# remote_control.net
KiCad netlist of a schematic drawn in Altium Designer
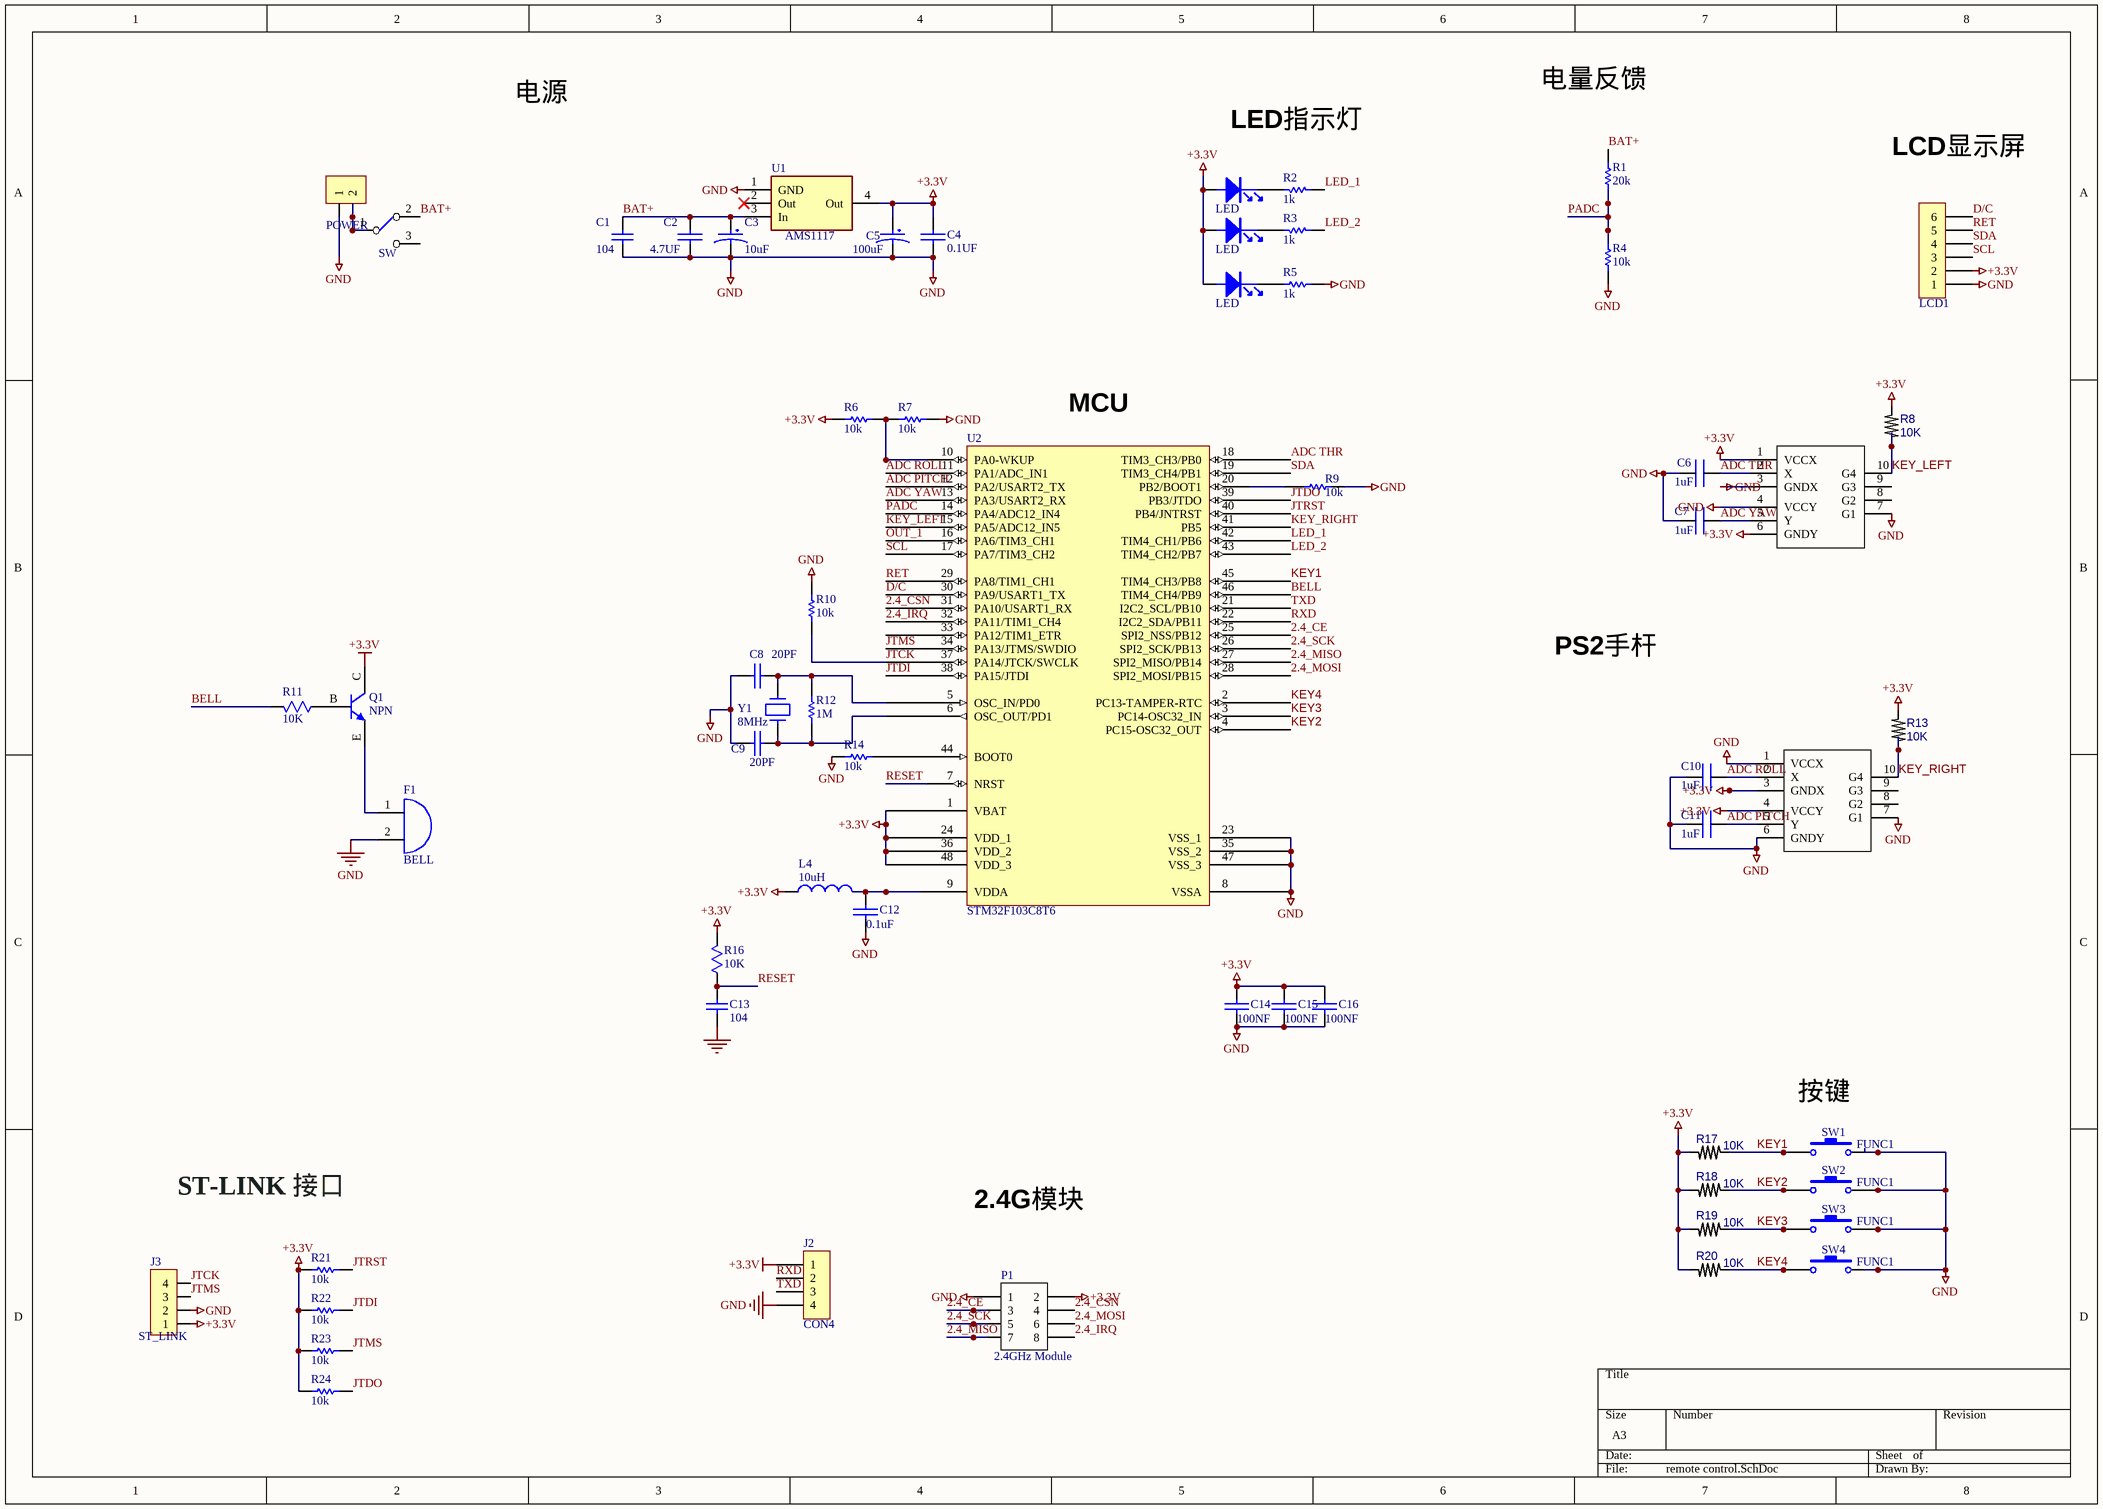
[diagram p0: remote control.SchDoc]

(export (version "E")
  (design (tool "Eeschema 10.0.6"))
  (components
    (comp (ref "C1")
      (value "104")
      (footprint "0805C")
      (description "Capacitor")
      (fields (field (name "PUBLISHER") "Altium Limited"))
      (libsource (lib "*") (part "Cap"))
    )
    (comp (ref "C2")
      (value "4.7UF")
      (footprint "1206C")
      (description "Capacitor/小容量电容")
      (libsource (lib "狗尾巴草设计室") (part "CAP"))
    )
    (comp (ref "C3")
      (value "CAPE")
      (footprint "C_EC")
      (fields (field (name "VAL") "10uF"))
      (libsource (lib "CommonSCH") (part "CAPE"))
    )
    (comp (ref "C4")
      (value "0.1UF")
      (footprint "0805C")
      (description "Capacitor/小容量电容")
      (libsource (lib "狗尾巴草设计室") (part "CAP"))
    )
    (comp (ref "C5")
      (value "CAPE")
      (footprint "C_ED8")
      (fields (field (name "VAL") "100uF"))
      (libsource (lib "CommonSCH") (part "CAPE"))
    )
    (comp (ref "C6") (value "1uF") (footprint "0805C") (libsource (lib "分立元件") (part "CAP")))
    (comp (ref "C7") (value "1uF") (footprint "0805") (libsource (lib "分立元件") (part "CAP")))
    (comp (ref "C8")
      (value "20PF")
      (footprint "0805C")
      (description "Capacitor/小容量电容")
      (libsource (lib "狗尾巴草设计室") (part "CAP"))
    )
    (comp (ref "C9")
      (value "20PF")
      (footprint "0805C")
      (description "Capacitor/小容量电容")
      (libsource (lib "狗尾巴草设计室") (part "CAP"))
    )
    (comp (ref "C10") (value "1uF") (footprint "0805") (libsource (lib "分立元件") (part "CAP")))
    (comp (ref "C11") (value "1uF") (footprint "0805") (libsource (lib "分立元件") (part "CAP")))
    (comp (ref "C12")
      (value "0.1uF")
      (footprint "0805C")
      (description "Capacitor/小容量电容")
      (libsource (lib "狗尾巴草设计室") (part "CAP"))
    )
    (comp (ref "C13")
      (value "104")
      (footprint "0805C")
      (description "GRM39 X7R102K50PT")
      (fields (field (name "PUBLISHER") "Altium Limited"))
      (libsource (lib "Miscellaneous Devices") (part "CAP"))
    )
    (comp (ref "C14")
      (value "100NF")
      (footprint "0805C")
      (description "Capacitor/小容量电容")
      (libsource (lib "狗尾巴草设计室") (part "CAP"))
    )
    (comp (ref "C15")
      (value "100NF")
      (footprint "0805C")
      (description "Capacitor/小容量电容")
      (libsource (lib "狗尾巴草设计室") (part "CAP"))
    )
    (comp (ref "C16")
      (value "100NF")
      (footprint "0805C")
      (description "Capacitor/小容量电容")
      (libsource (lib "狗尾巴草设计室") (part "CAP"))
    )
    (comp (ref "control_L1")
      (value "Joy Stick")
      (footprint "PS2")
      (description "Header, 10-Pin, Dual row")
      (fields (field (name "PUBLISHER") "Altium Limited"))
      (libsource (lib "1RMB") (part "Joy Stick"))
    )
    (comp (ref "control_R1")
      (value "Joy Stick")
      (footprint "PS2")
      (description "Header, 10-Pin, Dual row")
      (fields (field (name "PUBLISHER") "Altium Limited"))
      (libsource (lib "1RMB") (part "Joy Stick"))
    )
    (comp (ref "F1") (value "BELL") (footprint "BELL") (libsource (lib "狗尾巴草设计室") (part "BELL")))
    (comp (ref "J1") (value "POWER") (footprint "SIP2") (libsource (lib "狗尾巴草设计室") (part "SIP2")))
    (comp (ref "J2") (value "CON4") (footprint "SIP4") (libsource (lib "常用元件库") (part "CON4")))
    (comp (ref "J3") (value "ST_LINK") (footprint "P4_2.54-1") (libsource (lib "狗尾巴草设计室") (part "SIP4")))
    (comp (ref "L1") (value "LED") (footprint "0805D") (libsource (lib "ZF_library") (part "LED")))
    (comp (ref "L2") (value "LED") (footprint "0805D") (libsource (lib "ZF_library") (part "LED")))
    (comp (ref "L3") (value "LED") (footprint "0805D") (libsource (lib "ZF_library") (part "LED")))
    (comp (ref "L4")
      (value "INDUCTOR")
      (footprint "0805")
      (fields (field (name "VAL") "10uH"))
      (libsource (lib "SCH") (part "INDUCTOR"))
    )
    (comp (ref "LCD1") (value "CON6") (footprint "SIP6") (libsource (lib "常用元件库") (part "CON6")))
    (comp (ref "P1")
      (value "2.4GHz Module")
      (footprint "2.4Gmedal")
      (description "Header, 10-Pin, Dual row")
      (fields (field (name "PUBLISHER") "Altium Limited"))
      (libsource (lib "*") (part "Header 4X2"))
    )
    (comp (ref "Q1") (value "NPN") (footprint "SOT-23(BEC-123)") (libsource (lib "狗尾巴草设计室") (part "NPN")))
    (comp (ref "R1")
      (value "RES")
      (footprint "0805")
      (description "Semiconductor Resistor")
      (fields (field (name "VAL") "20k") (field (name "PUBLISHER") "*"))
      (libsource (lib "SCH") (part "RES"))
    )
    (comp (ref "R2")
      (value "1k")
      (footprint "0805R")
      (description "Resistor")
      (fields (field (name "Comment") "Res1") (field (name "PUBLISHER") "Altium Limited"))
      (libsource (lib "ZF_library") (part "Res1"))
    )
    (comp (ref "R3")
      (value "1k")
      (footprint "0805R")
      (description "Resistor")
      (fields (field (name "Comment") "Res1") (field (name "PUBLISHER") "Altium Limited"))
      (libsource (lib "ZF_library") (part "Res1"))
    )
    (comp (ref "R4")
      (value "RES")
      (footprint "0805")
      (description "Semiconductor Resistor")
      (fields (field (name "VAL") "10k") (field (name "PUBLISHER") "*"))
      (libsource (lib "SCH") (part "RES"))
    )
    (comp (ref "R5")
      (value "1k")
      (footprint "0805R")
      (description "Resistor")
      (fields (field (name "Comment") "Res1") (field (name "PUBLISHER") "Altium Limited"))
      (libsource (lib "SCHLIB1") (part "Res1"))
    )
    (comp (ref "R6")
      (value "RES")
      (footprint "0805")
      (description "Semiconductor Resistor")
      (fields (field (name "VAL") "10k") (field (name "PUBLISHER") "*"))
      (libsource (lib "SCH") (part "RES"))
    )
    (comp (ref "R7")
      (value "RES")
      (footprint "0805R")
      (description "Semiconductor Resistor")
      (fields (field (name "VAL") "10k") (field (name "PUBLISHER") "*"))
      (libsource (lib "SCH") (part "RES"))
    )
    (comp (ref "R8") (value "10K") (footprint "0805R") (libsource (lib "*") (part "RES")))
    (comp (ref "R9")
      (value "RES")
      (footprint "0805R")
      (description "Semiconductor Resistor")
      (fields (field (name "VAL") "10k") (field (name "PUBLISHER") "*"))
      (libsource (lib "SCH") (part "RES"))
    )
    (comp (ref "R10")
      (value "RES")
      (footprint "0805R")
      (description "Semiconductor Resistor")
      (fields (field (name "VAL") "10k") (field (name "PUBLISHER") "*"))
      (libsource (lib "SCH") (part "RES"))
    )
    (comp (ref "R11") (value "10K") (footprint "0805R") (libsource (lib "YT1_SCH_99SE") (part "RES")))
    (comp (ref "R12")
      (value "RES")
      (footprint "0805R")
      (description "Semiconductor Resistor")
      (fields (field (name "VAL") "1M") (field (name "PUBLISHER") "*"))
      (libsource (lib "SCH") (part "RES"))
    )
    (comp (ref "R13") (value "10K") (footprint "0805R") (libsource (lib "*") (part "RES")))
    (comp (ref "R14")
      (value "RES")
      (footprint "0805R")
      (description "Semiconductor Resistor")
      (fields (field (name "VAL") "10k") (field (name "PUBLISHER") "*"))
      (libsource (lib "SCH") (part "RES"))
    )
    (comp (ref "R16") (value "10K") (footprint "0805R") (libsource (lib "YT1_SCH_99SE") (part "RES")))
    (comp (ref "R17") (value "10K") (footprint "0805C") (libsource (lib "*") (part "RES")))
    (comp (ref "R18") (value "10K") (footprint "0805C") (libsource (lib "*") (part "RES")))
    (comp (ref "R19") (value "10K") (footprint "0805C") (libsource (lib "*") (part "RES")))
    (comp (ref "R20") (value "10K") (footprint "0805C") (libsource (lib "*") (part "RES")))
    (comp (ref "R21")
      (value "RES")
      (footprint "0805R")
      (description "Semiconductor Resistor")
      (fields (field (name "VAL") "10k") (field (name "PUBLISHER") "*"))
      (libsource (lib "SCH") (part "RES"))
    )
    (comp (ref "R22")
      (value "RES")
      (footprint "0805R")
      (description "Semiconductor Resistor")
      (fields (field (name "VAL") "10k") (field (name "PUBLISHER") "*"))
      (libsource (lib "SCH") (part "RES"))
    )
    (comp (ref "R23")
      (value "RES")
      (footprint "0805R")
      (description "Semiconductor Resistor")
      (fields (field (name "VAL") "10k") (field (name "PUBLISHER") "*"))
      (libsource (lib "SCH") (part "RES"))
    )
    (comp (ref "R24")
      (value "RES")
      (footprint "0805R")
      (description "Semiconductor Resistor")
      (fields (field (name "VAL") "10k") (field (name "PUBLISHER") "*"))
      (libsource (lib "SCH") (part "RES"))
    )
    (comp (ref "S1")
      (value "SW")
      (footprint "KEY_DIP_12D07-4")
      (libsource (lib "AD_Lib_temp") (part "SW_拨动_小型"))
    )
    (comp (ref "SW1")
      (value "FUNC1")
      (footprint "KEY_SIM_6X6")
      (description "Switch")
      (fields (field (name "PUBLISHER") "Altium Limited"))
      (libsource (lib "Miscellaneous Devices") (part "SW-PB"))
    )
    (comp (ref "SW2")
      (value "FUNC1")
      (footprint "KEY_SIM_6X6")
      (description "Switch")
      (fields (field (name "PUBLISHER") "Altium Limited"))
      (libsource (lib "Miscellaneous Devices") (part "SW-PB"))
    )
    (comp (ref "SW3")
      (value "FUNC1")
      (footprint "KEY_SIM_6X6")
      (description "Switch")
      (fields (field (name "PUBLISHER") "Altium Limited"))
      (libsource (lib "Miscellaneous Devices") (part "SW-PB"))
    )
    (comp (ref "SW4")
      (value "FUNC1")
      (footprint "KEY_SIM_6X6")
      (description "Switch")
      (fields (field (name "PUBLISHER") "Altium Limited"))
      (libsource (lib "Miscellaneous Devices") (part "SW-PB"))
    )
    (comp (ref "U1")
      (value "AMS1117")
      (footprint "SOT223")
      (description "Header, 2-Pin")
      (fields (field (name "PUBLISHER") "*"))
      (libsource (lib "CommonSCH") (part "AMS1117"))
    )
    (comp (ref "U2")
      (value "STM32F103C8T6")
      (footprint "LQFP48")
      (description "STM32 ARM-based 32-bit MCU with 64 Kbytes Flash, 48-pin LQFP, Industrial Temperature")
      (fields (field (name "PUBLISHER") "*"))
      (libsource (lib "ZF_library") (part "STM32F103C8T6"))
    )
    (comp (ref "Y1")
      (value "CRYSTAL1")
      (footprint "HC-49T")
      (fields (field (name "VAL") "8MHz"))
      (libsource (lib "SCH") (part "CRYSTAL1"))
    )
  )
  (nets
    (net (code "1") (name "+3.3V") (class "Default")
      (node (ref "C14") (pin "1") (pinfunction "1_1") (pintype "passive"))
      (node (ref "C15") (pin "1") (pinfunction "1_1") (pintype "passive"))
      (node (ref "C16") (pin "1") (pinfunction "1_1") (pintype "passive"))
      (node (ref "C4") (pin "1") (pinfunction "1_1") (pintype "passive"))
      (node (ref "C5") (pin "1") (pinfunction "1_1") (pintype "passive"))
      (node (ref "J2") (pin "1") (pinfunction "1_1") (pintype "passive"))
      (node (ref "J3") (pin "1") (pinfunction "1_1") (pintype "passive"))
      (node (ref "L1") (pin "1") (pintype "passive"))
      (node (ref "L2") (pin "1") (pintype "passive"))
      (node (ref "L3") (pin "1") (pintype "passive"))
      (node (ref "L4") (pin "1") (pinfunction "1_1") (pintype "passive"))
      (node (ref "LCD1") (pin "2") (pinfunction "2_2") (pintype "passive"))
      (node (ref "P1") (pin "2") (pinfunction "2_2") (pintype "passive"))
      (node (ref "Q1") (pin "C") (pinfunction "C_C") (pintype "passive"))
      (node (ref "R13") (pin "2") (pinfunction "2_2") (pintype "passive"))
      (node (ref "R16") (pin "2") (pinfunction "2_2") (pintype "passive"))
      (node (ref "R17") (pin "1") (pinfunction "1_1") (pintype "passive"))
      (node (ref "R18") (pin "1") (pinfunction "1_1") (pintype "passive"))
      (node (ref "R19") (pin "1") (pinfunction "1_1") (pintype "passive"))
      (node (ref "R20") (pin "1") (pinfunction "1_1") (pintype "passive"))
      (node (ref "R21") (pin "2") (pinfunction "2_2") (pintype "passive"))
      (node (ref "R22") (pin "2") (pinfunction "2_2") (pintype "passive"))
      (node (ref "R23") (pin "2") (pinfunction "2_2") (pintype "passive"))
      (node (ref "R24") (pin "2") (pinfunction "2_2") (pintype "passive"))
      (node (ref "R6") (pin "2") (pinfunction "2_2") (pintype "passive"))
      (node (ref "R8") (pin "2") (pinfunction "2_2") (pintype "passive"))
      (node (ref "U1") (pin "4") (pinfunction "Out_4") (pintype "passive"))
      (node (ref "U2") (pin "1") (pinfunction "VBAT_1") (pintype "power_in"))
      (node (ref "U2") (pin "24") (pinfunction "VDD_1_24") (pintype "power_in"))
      (node (ref "U2") (pin "36") (pinfunction "VDD_2_36") (pintype "power_in"))
      (node (ref "U2") (pin "48") (pinfunction "VDD_3_48") (pintype "power_in"))
      (node (ref "control_L1") (pin "1") (pinfunction "VCCX_1") (pintype "passive"))
      (node (ref "control_L1") (pin "6") (pinfunction "GNDY_6") (pintype "passive"))
      (node (ref "control_R1") (pin "3") (pinfunction "GNDX_3") (pintype "passive"))
      (node (ref "control_R1") (pin "4") (pinfunction "VCCY_4") (pintype "passive"))
    )
    (net (code "2") (name "/2.4_CE") (class "Default")
      (node (ref "P1") (pin "3") (pinfunction "3_3") (pintype "passive"))
      (node (ref "U2") (pin "25") (pinfunction "SPI2_NSS/PB12_25") (pintype "bidirectional"))
    )
    (net (code "3") (name "/2.4_CSN") (class "Default")
      (node (ref "P1") (pin "4") (pinfunction "4_4") (pintype "passive"))
      (node (ref "U2") (pin "31") (pinfunction "PA10/USART1_RX_31") (pintype "bidirectional"))
    )
    (net (code "4") (name "/2.4_IRQ") (class "Default")
      (node (ref "P1") (pin "8") (pinfunction "8_8") (pintype "passive"))
      (node (ref "U2") (pin "32") (pinfunction "PA11/TIM1_CH4_32") (pintype "bidirectional"))
    )
    (net (code "5") (name "/2.4_MISO") (class "Default")
      (node (ref "P1") (pin "7") (pinfunction "7_7") (pintype "passive"))
      (node (ref "U2") (pin "27") (pinfunction "SPI2_MISO/PB14_27") (pintype "bidirectional"))
    )
    (net (code "6") (name "/2.4_MOSI") (class "Default")
      (node (ref "P1") (pin "6") (pinfunction "6_6") (pintype "passive"))
      (node (ref "U2") (pin "28") (pinfunction "SPI2_MOSI/PB15_28") (pintype "bidirectional"))
    )
    (net (code "7") (name "/2.4_SCK") (class "Default")
      (node (ref "P1") (pin "5") (pinfunction "5_5") (pintype "passive"))
      (node (ref "U2") (pin "26") (pinfunction "SPI2_SCK/PB13_26") (pintype "bidirectional"))
    )
    (net (code "8") (name "/ADC PITCH") (class "Default")
      (node (ref "C11") (pin "2") (pinfunction "2_2") (pintype "passive"))
      (node (ref "U2") (pin "12") (pinfunction "PA2/USART2_TX_12") (pintype "bidirectional"))
      (node (ref "control_R1") (pin "5") (pinfunction "Y_5") (pintype "passive"))
    )
    (net (code "9") (name "/ADC ROLL") (class "Default")
      (node (ref "C10") (pin "2") (pinfunction "2_2") (pintype "passive"))
      (node (ref "U2") (pin "11") (pinfunction "PA1/ADC_IN1_11") (pintype "bidirectional"))
      (node (ref "control_R1") (pin "2") (pinfunction "X_2") (pintype "passive"))
    )
    (net (code "10") (name "/ADC THR") (class "Default")
      (node (ref "C6") (pin "2") (pinfunction "2_2") (pintype "passive"))
      (node (ref "U2") (pin "18") (pinfunction "TIM3_CH3/PB0_18") (pintype "bidirectional"))
      (node (ref "control_L1") (pin "2") (pinfunction "X_2") (pintype "passive"))
    )
    (net (code "11") (name "/ADC YAW") (class "Default")
      (node (ref "C7") (pin "2") (pinfunction "2_2") (pintype "passive"))
      (node (ref "U2") (pin "13") (pinfunction "PA3/USART2_RX_13") (pintype "bidirectional"))
      (node (ref "control_L1") (pin "5") (pinfunction "Y_5") (pintype "passive"))
    )
    (net (code "12") (name "/BAT+") (class "Default")
      (node (ref "C1") (pin "1") (pinfunction "1_1") (pintype "passive"))
      (node (ref "C2") (pin "1") (pinfunction "1_1") (pintype "passive"))
      (node (ref "C3") (pin "1") (pinfunction "1_1") (pintype "passive"))
      (node (ref "R1") (pin "2") (pinfunction "2_2") (pintype "passive"))
      (node (ref "S1") (pin "2") (pinfunction "1_2") (pintype "passive"))
      (node (ref "U1") (pin "3") (pinfunction "In_3") (pintype "passive"))
    )
    (net (code "13") (name "/BELL") (class "Default")
      (node (ref "R11") (pin "2") (pinfunction "2_2") (pintype "passive"))
      (node (ref "U2") (pin "46") (pinfunction "TIM4_CH4/PB9_46") (pintype "bidirectional"))
    )
    (net (code "14") (name "/D{slash}C") (class "Default")
      (node (ref "LCD1") (pin "6") (pinfunction "6_6") (pintype "passive"))
      (node (ref "U2") (pin "30") (pinfunction "PA9/USART1_TX_30") (pintype "bidirectional"))
    )
    (net (code "15") (name "/JTCK") (class "Default")
      (node (ref "J3") (pin "4") (pinfunction "4_4") (pintype "passive"))
      (node (ref "R10") (pin "1") (pinfunction "1_1") (pintype "passive"))
      (node (ref "U2") (pin "37") (pinfunction "PA14/JTCK/SWCLK_37") (pintype "bidirectional"))
    )
    (net (code "16") (name "/JTDI") (class "Default")
      (node (ref "R22") (pin "1") (pinfunction "1_1") (pintype "passive"))
      (node (ref "U2") (pin "38") (pinfunction "PA15/JTDI_38") (pintype "bidirectional"))
    )
    (net (code "17") (name "/JTDO") (class "Default")
      (node (ref "R24") (pin "1") (pinfunction "1_1") (pintype "passive"))
      (node (ref "U2") (pin "39") (pinfunction "PB3/JTDO_39") (pintype "bidirectional"))
    )
    (net (code "18") (name "/JTMS") (class "Default")
      (node (ref "J3") (pin "3") (pinfunction "3_3") (pintype "passive"))
      (node (ref "R23") (pin "1") (pinfunction "1_1") (pintype "passive"))
      (node (ref "U2") (pin "34") (pinfunction "PA13/JTMS/SWDIO_34") (pintype "bidirectional"))
    )
    (net (code "19") (name "/JTRST") (class "Default")
      (node (ref "R21") (pin "1") (pinfunction "1_1") (pintype "passive"))
      (node (ref "U2") (pin "40") (pinfunction "PB4/JNTRST_40") (pintype "bidirectional"))
    )
    (net (code "20") (name "/KEY1") (class "Default")
      (node (ref "R17") (pin "2") (pinfunction "2_2") (pintype "passive"))
      (node (ref "SW1") (pin "2") (pinfunction "2_2") (pintype "passive"))
      (node (ref "U2") (pin "45") (pinfunction "TIM4_CH3/PB8_45") (pintype "bidirectional"))
    )
    (net (code "21") (name "/KEY2") (class "Default")
      (node (ref "R18") (pin "2") (pinfunction "2_2") (pintype "passive"))
      (node (ref "SW2") (pin "2") (pinfunction "2_2") (pintype "passive"))
      (node (ref "U2") (pin "4") (pinfunction "PC15-OSC32_OUT_4") (pintype "bidirectional"))
    )
    (net (code "22") (name "/KEY3") (class "Default")
      (node (ref "R19") (pin "2") (pinfunction "2_2") (pintype "passive"))
      (node (ref "SW3") (pin "2") (pinfunction "2_2") (pintype "passive"))
      (node (ref "U2") (pin "3") (pinfunction "PC14-OSC32_IN_3") (pintype "bidirectional"))
    )
    (net (code "23") (name "/KEY4") (class "Default")
      (node (ref "R20") (pin "2") (pinfunction "2_2") (pintype "passive"))
      (node (ref "SW4") (pin "2") (pinfunction "2_2") (pintype "passive"))
      (node (ref "U2") (pin "2") (pinfunction "PC13-TAMPER-RTC_2") (pintype "bidirectional"))
    )
    (net (code "24") (name "/KEY_LEFT") (class "Default")
      (node (ref "R8") (pin "1") (pinfunction "1_1") (pintype "passive"))
      (node (ref "U2") (pin "15") (pinfunction "PA5/ADC12_IN5_15") (pintype "bidirectional"))
      (node (ref "control_L1") (pin "10") (pinfunction "G4_10") (pintype "passive"))
    )
    (net (code "25") (name "/KEY_RIGHT") (class "Default")
      (node (ref "R13") (pin "1") (pinfunction "1_1") (pintype "passive"))
      (node (ref "U2") (pin "41") (pinfunction "PB5_41") (pintype "bidirectional"))
      (node (ref "control_R1") (pin "10") (pinfunction "G4_10") (pintype "passive"))
    )
    (net (code "26") (name "/LED_1") (class "Default")
      (node (ref "R2") (pin "1") (pinfunction "1_1") (pintype "passive"))
      (node (ref "U2") (pin "42") (pinfunction "TIM4_CH1/PB6_42") (pintype "bidirectional"))
    )
    (net (code "27") (name "/LED_2") (class "Default")
      (node (ref "R3") (pin "1") (pinfunction "1_1") (pintype "passive"))
      (node (ref "U2") (pin "43") (pinfunction "TIM4_CH2/PB7_43") (pintype "bidirectional"))
    )
    (net (code "28") (name "/OUT_1") (class "Default")
      (node (ref "U2") (pin "16") (pinfunction "PA6/TIM3_CH1_16") (pintype "bidirectional"))
    )
    (net (code "29") (name "/PADC") (class "Default")
      (node (ref "R1") (pin "1") (pinfunction "1_1") (pintype "passive"))
      (node (ref "R4") (pin "2") (pinfunction "2_2") (pintype "passive"))
      (node (ref "U2") (pin "14") (pinfunction "PA4/ADC12_IN4_14") (pintype "bidirectional"))
    )
    (net (code "30") (name "/RESET") (class "Default")
      (node (ref "C13") (pin "2") (pinfunction "2_2") (pintype "passive"))
      (node (ref "R16") (pin "1") (pinfunction "1_1") (pintype "passive"))
      (node (ref "U2") (pin "7") (pinfunction "NRST_7") (pintype "bidirectional"))
    )
    (net (code "31") (name "/RET") (class "Default")
      (node (ref "LCD1") (pin "5") (pinfunction "5_5") (pintype "passive"))
      (node (ref "U2") (pin "29") (pinfunction "PA8/TIM1_CH1_29") (pintype "bidirectional"))
    )
    (net (code "32") (name "/RXD") (class "Default")
      (node (ref "J2") (pin "2") (pinfunction "2_2") (pintype "passive"))
      (node (ref "U2") (pin "22") (pinfunction "I2C2_SDA/PB11_22") (pintype "bidirectional"))
    )
    (net (code "33") (name "/SCL") (class "Default")
      (node (ref "LCD1") (pin "3") (pinfunction "3_3") (pintype "passive"))
      (node (ref "U2") (pin "17") (pinfunction "PA7/TIM3_CH2_17") (pintype "bidirectional"))
    )
    (net (code "34") (name "/SDA") (class "Default")
      (node (ref "LCD1") (pin "4") (pinfunction "4_4") (pintype "passive"))
      (node (ref "U2") (pin "19") (pinfunction "TIM3_CH4/PB1_19") (pintype "bidirectional"))
    )
    (net (code "35") (name "/TXD") (class "Default")
      (node (ref "J2") (pin "3") (pinfunction "3_3") (pintype "passive"))
      (node (ref "U2") (pin "21") (pinfunction "I2C2_SCL/PB10_21") (pintype "bidirectional"))
    )
    (net (code "36") (name "GND") (class "Default")
      (node (ref "C1") (pin "2") (pinfunction "2_2") (pintype "passive"))
      (node (ref "C10") (pin "1") (pinfunction "1_1") (pintype "passive"))
      (node (ref "C11") (pin "1") (pinfunction "1_1") (pintype "passive"))
      (node (ref "C12") (pin "2") (pinfunction "2_2") (pintype "passive"))
      (node (ref "C13") (pin "1") (pinfunction "1_1") (pintype "passive"))
      (node (ref "C14") (pin "2") (pinfunction "2_2") (pintype "passive"))
      (node (ref "C15") (pin "2") (pinfunction "2_2") (pintype "passive"))
      (node (ref "C16") (pin "2") (pinfunction "2_2") (pintype "passive"))
      (node (ref "C2") (pin "2") (pinfunction "2_2") (pintype "passive"))
      (node (ref "C3") (pin "2") (pinfunction "2_2") (pintype "passive"))
      (node (ref "C4") (pin "2") (pinfunction "2_2") (pintype "passive"))
      (node (ref "C5") (pin "2") (pinfunction "2_2") (pintype "passive"))
      (node (ref "C6") (pin "1") (pinfunction "1_1") (pintype "passive"))
      (node (ref "C7") (pin "1") (pinfunction "1_1") (pintype "passive"))
      (node (ref "C8") (pin "1") (pinfunction "1_1") (pintype "passive"))
      (node (ref "C9") (pin "1") (pinfunction "1_1") (pintype "passive"))
      (node (ref "F1") (pin "2") (pinfunction "B_2") (pintype "passive"))
      (node (ref "J1") (pin "1") (pinfunction "1_1") (pintype "passive"))
      (node (ref "J2") (pin "4") (pinfunction "4_4") (pintype "passive"))
      (node (ref "J3") (pin "2") (pinfunction "2_2") (pintype "passive"))
      (node (ref "LCD1") (pin "1") (pinfunction "1_1") (pintype "passive"))
      (node (ref "P1") (pin "1") (pinfunction "1_1") (pintype "passive"))
      (node (ref "R10") (pin "2") (pinfunction "2_2") (pintype "passive"))
      (node (ref "R14") (pin "2") (pinfunction "2_2") (pintype "passive"))
      (node (ref "R4") (pin "1") (pinfunction "1_1") (pintype "passive"))
      (node (ref "R5") (pin "1") (pinfunction "1_1") (pintype "passive"))
      (node (ref "R7") (pin "1") (pinfunction "1_1") (pintype "passive"))
      (node (ref "R9") (pin "2") (pinfunction "2_2") (pintype "passive"))
      (node (ref "SW1") (pin "1") (pinfunction "1_1") (pintype "passive"))
      (node (ref "SW2") (pin "1") (pinfunction "1_1") (pintype "passive"))
      (node (ref "SW3") (pin "1") (pinfunction "1_1") (pintype "passive"))
      (node (ref "SW4") (pin "1") (pinfunction "1_1") (pintype "passive"))
      (node (ref "U1") (pin "1") (pinfunction "GND_1") (pintype "passive"))
      (node (ref "U2") (pin "23") (pinfunction "VSS_1_23") (pintype "power_in"))
      (node (ref "U2") (pin "35") (pinfunction "VSS_2_35") (pintype "power_in"))
      (node (ref "U2") (pin "47") (pinfunction "VSS_3_47") (pintype "power_in"))
      (node (ref "U2") (pin "8") (pinfunction "VSSA_8") (pintype "power_in"))
      (node (ref "control_L1") (pin "3") (pinfunction "GNDX_3") (pintype "passive"))
      (node (ref "control_L1") (pin "4") (pinfunction "VCCY_4") (pintype "passive"))
      (node (ref "control_L1") (pin "7") (pinfunction "G1_7") (pintype "passive"))
      (node (ref "control_R1") (pin "1") (pinfunction "VCCX_1") (pintype "passive"))
      (node (ref "control_R1") (pin "6") (pinfunction "GNDY_6") (pintype "passive"))
      (node (ref "control_R1") (pin "7") (pinfunction "G1_7") (pintype "passive"))
    )
    (net (code "37") (name "Net-(F1-A)") (class "Default")
      (node (ref "F1") (pin "1") (pinfunction "A_1") (pintype "passive"))
      (node (ref "Q1") (pin "E") (pinfunction "E_E") (pintype "passive"))
    )
    (net (code "38") (name "Net-(L1-Pad2)") (class "Default")
      (node (ref "L1") (pin "2") (pintype "passive"))
      (node (ref "R2") (pin "2") (pinfunction "2_2") (pintype "passive"))
    )
    (net (code "39") (name "Net-(L2-Pad2)") (class "Default")
      (node (ref "L2") (pin "2") (pintype "passive"))
      (node (ref "R3") (pin "2") (pinfunction "2_2") (pintype "passive"))
    )
    (net (code "40") (name "Net-(L3-Pad2)") (class "Default")
      (node (ref "L3") (pin "2") (pintype "passive"))
      (node (ref "R5") (pin "2") (pinfunction "2_2") (pintype "passive"))
    )
    (net (code "41") (name "Net-(Q1-PadB)") (class "Default")
      (node (ref "Q1") (pin "B") (pinfunction "B_B") (pintype "passive"))
      (node (ref "R11") (pin "1") (pinfunction "1_1") (pintype "passive"))
    )
    (net (code "42") (name "Net-(S1-2)") (class "Default")
      (node (ref "J1") (pin "2") (pinfunction "2_2") (pintype "passive"))
      (node (ref "S1") (pin "1") (pinfunction "2_1") (pintype "passive"))
    )
    (net (code "43") (name "Net-(U2-BOOT0)") (class "Default")
      (node (ref "R14") (pin "1") (pinfunction "1_1") (pintype "passive"))
      (node (ref "U2") (pin "44") (pinfunction "BOOT0_44") (pintype "input"))
    )
    (net (code "44") (name "Net-(U2-OSC_IN{slash}PD0)") (class "Default")
      (node (ref "C8") (pin "2") (pinfunction "2_2") (pintype "passive"))
      (node (ref "R12") (pin "2") (pinfunction "2_2") (pintype "passive"))
      (node (ref "U2") (pin "5") (pinfunction "OSC_IN/PD0_5") (pintype "input"))
      (node (ref "Y1") (pin "2") (pinfunction "2_2") (pintype "passive"))
    )
    (net (code "45") (name "Net-(U2-OSC_OUT{slash}PD1)") (class "Default")
      (node (ref "C9") (pin "2") (pinfunction "2_2") (pintype "passive"))
      (node (ref "R12") (pin "1") (pinfunction "1_1") (pintype "passive"))
      (node (ref "U2") (pin "6") (pinfunction "OSC_OUT/PD1_6") (pintype "output"))
      (node (ref "Y1") (pin "1") (pinfunction "1_1") (pintype "passive"))
    )
    (net (code "46") (name "Net-(U2-PA0-WKUP)") (class "Default")
      (node (ref "R6") (pin "1") (pinfunction "1_1") (pintype "passive"))
      (node (ref "R7") (pin "2") (pinfunction "2_2") (pintype "passive"))
      (node (ref "U2") (pin "10") (pinfunction "PA0-WKUP_10") (pintype "bidirectional"))
    )
    (net (code "47") (name "Net-(U2-PB2{slash}BOOT1)") (class "Default")
      (node (ref "R9") (pin "1") (pinfunction "1_1") (pintype "passive"))
      (node (ref "U2") (pin "20") (pinfunction "PB2/BOOT1_20") (pintype "bidirectional"))
    )
    (net (code "48") (name "Net-(U2-VDDA)") (class "Default")
      (node (ref "C12") (pin "1") (pinfunction "1_1") (pintype "passive"))
      (node (ref "L4") (pin "2") (pinfunction "2_2") (pintype "passive"))
      (node (ref "U2") (pin "9") (pinfunction "VDDA_9") (pintype "power_in"))
    )
    (net (code "49") (name "unconnected-(S1-Pad3)") (class "Default")
      (node (ref "S1") (pin "3") (pinfunction "3_3") (pintype "passive"))
    )
    (net (code "50") (name "unconnected-(U1-Out-Pad2)") (class "Default")
      (node (ref "U1") (pin "2") (pinfunction "Out_2") (pintype "passive+no_connect"))
    )
    (net (code "51") (name "unconnected-(U2-PA12{slash}TIM1_ETR-Pad33)") (class "Default")
      (node (ref "U2") (pin "33") (pinfunction "PA12/TIM1_ETR_33") (pintype "bidirectional"))
    )
    (net (code "52") (name "unconnected-(control_L1-G2-Pad8)") (class "Default")
      (node (ref "control_L1") (pin "8") (pinfunction "G2_8") (pintype "passive"))
    )
    (net (code "53") (name "unconnected-(control_L1-G3-Pad9)") (class "Default")
      (node (ref "control_L1") (pin "9") (pinfunction "G3_9") (pintype "passive"))
    )
    (net (code "54") (name "unconnected-(control_R1-G2-Pad8)") (class "Default")
      (node (ref "control_R1") (pin "8") (pinfunction "G2_8") (pintype "passive"))
    )
    (net (code "55") (name "unconnected-(control_R1-G3-Pad9)") (class "Default")
      (node (ref "control_R1") (pin "9") (pinfunction "G3_9") (pintype "passive"))
    )
  )
)
